# Regulator.net
KiCad netlist of a schematic drawn in EAGLE
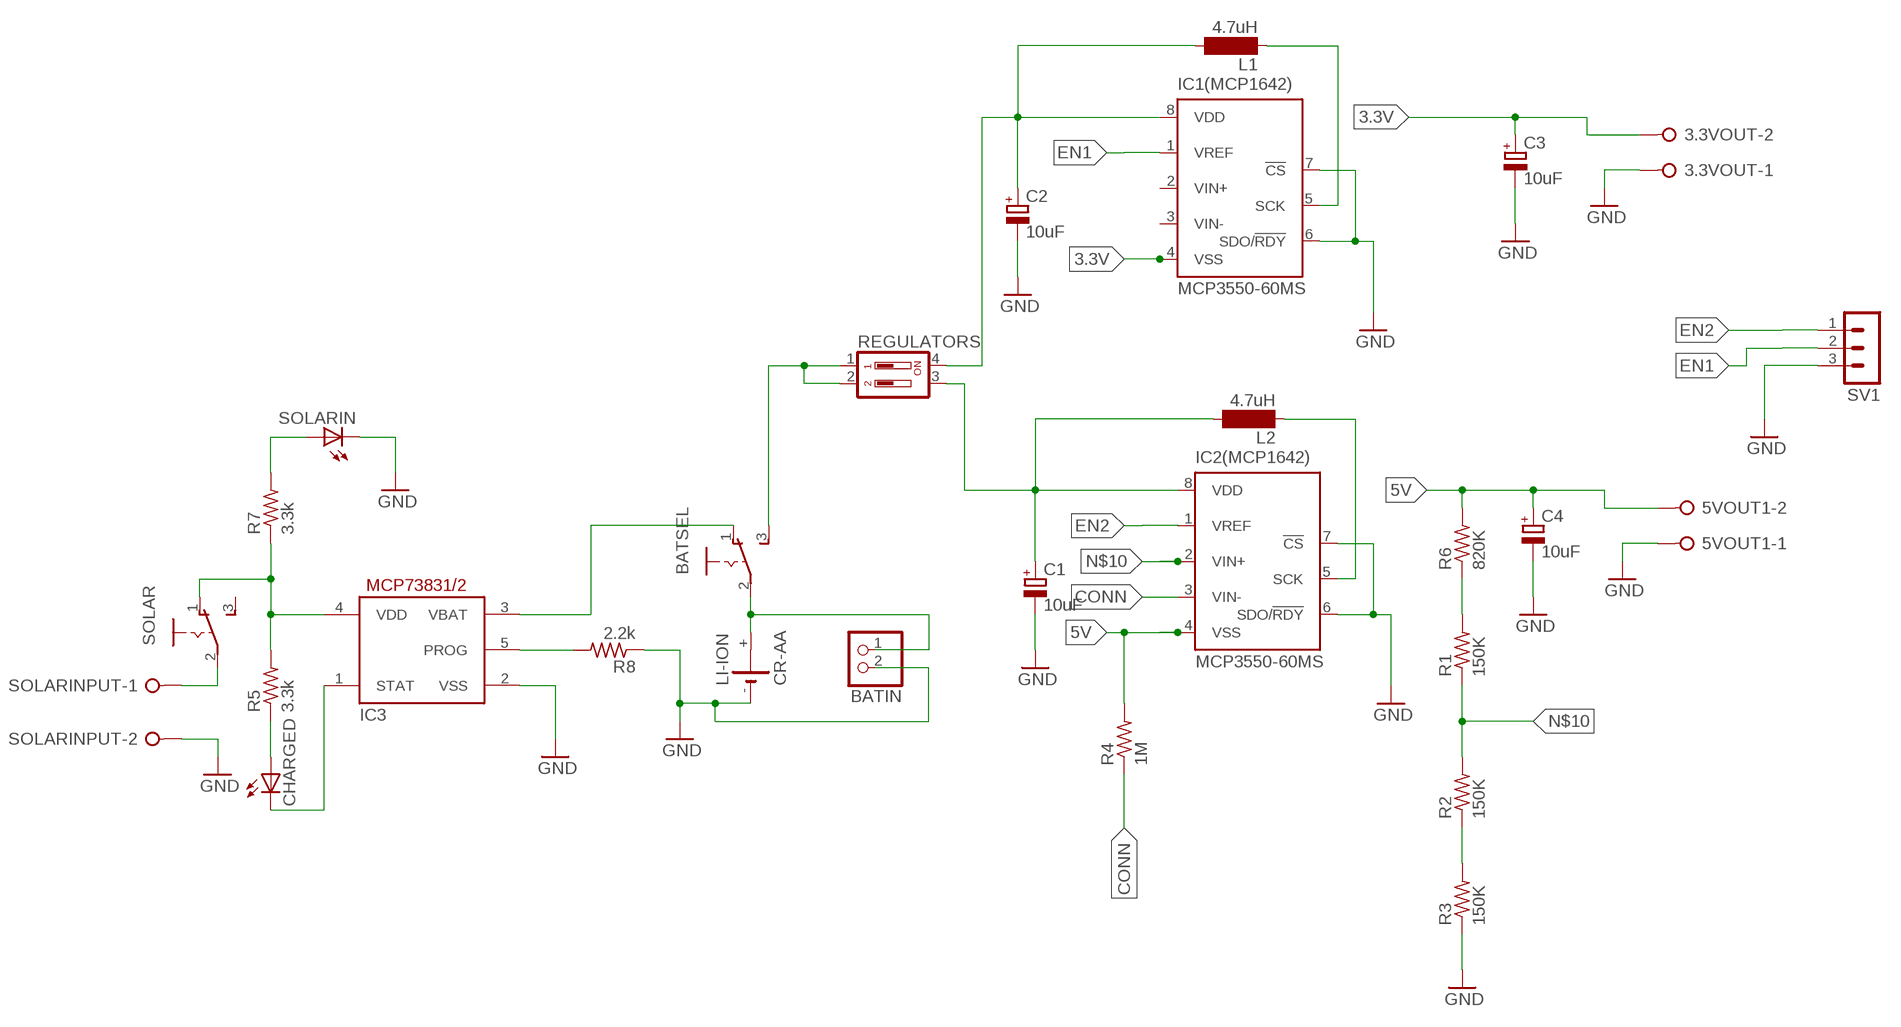
[diagram p0: schematic, sheet 1]

(export (version "E")
  (design (tool "Eeschema 10.0.6"))
  (components
    (comp (ref "3.3VOUT")
      (value "W237-02P")
      (footprint "eagle-import:W237-132")
      (libsource (lib "eagle-import") (part "W237-02P"))
    )
    (comp (ref "5VOUT1")
      (value "W237-02P")
      (footprint "eagle-import:W237-132")
      (libsource (lib "eagle-import") (part "W237-02P"))
    )
    (comp (ref "BATIN")
      (value "JST_2PIN-THM")
      (footprint "eagle-import:JST-PH-2-THM")
      (libsource (lib "eagle-import") (part "JST_2PIN-THM"))
    )
    (comp (ref "BATSEL")
      (value "255SB")
      (footprint "eagle-import:255SB")
      (libsource (lib "eagle-import") (part "255SB"))
    )
    (comp (ref "C1")
      (value "10uF")
      (footprint "eagle-import:140CLH-1010")
      (libsource (lib "eagle-import") (part "CPOL-EU140CLH-1010"))
    )
    (comp (ref "C2")
      (value "10uF")
      (footprint "eagle-import:140CLH-1010")
      (libsource (lib "eagle-import") (part "CPOL-EU140CLH-1010"))
    )
    (comp (ref "C3")
      (value "10uF")
      (footprint "eagle-import:140CLH-1010")
      (libsource (lib "eagle-import") (part "CPOL-EU140CLH-1010"))
    )
    (comp (ref "C4")
      (value "10uF")
      (footprint "eagle-import:140CLH-1010")
      (libsource (lib "eagle-import") (part "CPOL-EU140CLH-1010"))
    )
    (comp (ref "CHARGED")
      (value "LEDCHIP-LED0603")
      (footprint "eagle-import:CHIP-LED0603")
      (libsource (lib "eagle-import") (part "LEDCHIP-LED0603"))
    )
    (comp (ref "IC1(MCP1642)")
      (value "MCP3550-60MS")
      (footprint "eagle-import:MSOP8")
      (fields (field (name "MF") "MICROCHIP") (field (name "MPN") "MCP3550-60E/MS"))
      (libsource (lib "eagle-import") (part "MCP355MS0-60"))
    )
    (comp (ref "IC2(MCP1642)")
      (value "MCP3550-60MS")
      (footprint "eagle-import:MSOP8")
      (fields (field (name "MF") "MICROCHIP") (field (name "MPN") "MCP3550-60E/MS"))
      (libsource (lib "eagle-import") (part "MCP355MS0-60"))
    )
    (comp (ref "IC3")
      (value "MCP73831/OT")
      (footprint "eagle-import:SOT23-5L")
      (libsource (lib "eagle-import") (part "MCP73831/OT"))
    )
    (comp (ref "L1")
      (value "4.7uH")
      (footprint "eagle-import:MS85")
      (libsource (lib "eagle-import") (part "MS85"))
    )
    (comp (ref "L2")
      (value "4.7uH")
      (footprint "eagle-import:MS85")
      (libsource (lib "eagle-import") (part "MS85"))
    )
    (comp (ref "LI-ION")
      (value "CR-AA")
      (footprint "eagle-import:CRAA")
      (libsource (lib "eagle-import") (part "CR-AA"))
    )
    (comp (ref "R1")
      (value "150K")
      (footprint "eagle-import:M0805")
      (libsource (lib "eagle-import") (part "R-US_M0805"))
    )
    (comp (ref "R2")
      (value "150K")
      (footprint "eagle-import:M0805")
      (libsource (lib "eagle-import") (part "R-US_M0805"))
    )
    (comp (ref "R3")
      (value "150K")
      (footprint "eagle-import:M0805")
      (libsource (lib "eagle-import") (part "R-US_M0805"))
    )
    (comp (ref "R4")
      (value "1M")
      (footprint "eagle-import:M0805")
      (libsource (lib "eagle-import") (part "R-US_M0805"))
    )
    (comp (ref "R5")
      (value "3.3k")
      (footprint "eagle-import:M3216")
      (libsource (lib "eagle-import") (part "R-US_M3216"))
    )
    (comp (ref "R6")
      (value "820K")
      (footprint "eagle-import:M0805")
      (libsource (lib "eagle-import") (part "R-US_M0805"))
    )
    (comp (ref "R7")
      (value "3.3k")
      (footprint "eagle-import:M3216")
      (libsource (lib "eagle-import") (part "R-US_M3216"))
    )
    (comp (ref "R8")
      (value "2.2k")
      (footprint "eagle-import:M3216")
      (libsource (lib "eagle-import") (part "R-US_M3216"))
    )
    (comp (ref "REGULATORS")
      (value "DIP02YL")
      (footprint "eagle-import:DIP02YL")
      (libsource (lib "eagle-import") (part "DIP02YL"))
    )
    (comp (ref "SOLAR")
      (value "255SB")
      (footprint "eagle-import:255SB")
      (libsource (lib "eagle-import") (part "255SB"))
    )
    (comp (ref "SOLARIN")
      (value "LEDCHIP-LED0603")
      (footprint "eagle-import:CHIP-LED0603")
      (libsource (lib "eagle-import") (part "LEDCHIP-LED0603"))
    )
    (comp (ref "SOLARINPUT")
      (value "W237-02P")
      (footprint "eagle-import:W237-132")
      (libsource (lib "eagle-import") (part "W237-02P"))
    )
    (comp (ref "SV1")
      (value "MA03-1")
      (footprint "eagle-import:MA03-1")
      (libsource (lib "eagle-import") (part "MA03-1"))
    )
  )
  (nets
    (net (code "1") (name "3.3V") (class "Default")
      (node (ref "3.3VOUT") (pin "2") (pinfunction "KL_2") (pintype "passive"))
      (node (ref "C3") (pin "+") (pinfunction "+_+") (pintype "passive"))
      (node (ref "IC1(MCP1642)") (pin "4") (pinfunction "VSS_4") (pintype "power_in"))
    )
    (net (code "2") (name "5V") (class "Default")
      (node (ref "5VOUT1") (pin "2") (pinfunction "KL_2") (pintype "passive"))
      (node (ref "C4") (pin "+") (pinfunction "+_+") (pintype "passive"))
      (node (ref "IC2(MCP1642)") (pin "4") (pinfunction "VSS_4") (pintype "power_in"))
      (node (ref "R4") (pin "2") (pinfunction "2_2") (pintype "passive"))
      (node (ref "R6") (pin "2") (pinfunction "2_2") (pintype "passive"))
    )
    (net (code "3") (name "CONN") (class "Default")
      (node (ref "IC2(MCP1642)") (pin "3") (pinfunction "VIN-_3") (pintype "input"))
      (node (ref "R4") (pin "1") (pinfunction "1_1") (pintype "passive"))
    )
    (net (code "4") (name "EN1") (class "Default")
      (node (ref "IC1(MCP1642)") (pin "1") (pinfunction "VREF_1") (pintype "input"))
      (node (ref "SV1") (pin "2") (pinfunction "2_2") (pintype "passive"))
    )
    (net (code "5") (name "EN2") (class "Default")
      (node (ref "IC2(MCP1642)") (pin "1") (pinfunction "VREF_1") (pintype "input"))
      (node (ref "SV1") (pin "1") (pinfunction "1_1") (pintype "passive"))
    )
    (net (code "6") (name "GND") (class "Default")
      (node (ref "3.3VOUT") (pin "1") (pinfunction "KL_1") (pintype "passive"))
      (node (ref "5VOUT1") (pin "1") (pinfunction "KL_1") (pintype "passive"))
      (node (ref "BATIN") (pin "2") (pinfunction "1_2") (pintype "passive"))
      (node (ref "C1") (pin "-") (pinfunction "-_-") (pintype "passive"))
      (node (ref "C2") (pin "-") (pinfunction "-_-") (pintype "passive"))
      (node (ref "C3") (pin "-") (pinfunction "-_-") (pintype "passive"))
      (node (ref "C4") (pin "-") (pinfunction "-_-") (pintype "passive"))
      (node (ref "IC1(MCP1642)") (pin "6") (pinfunction "SDO/~{RDY}_6") (pintype "output"))
      (node (ref "IC1(MCP1642)") (pin "7") (pinfunction "~{CS}_7") (pintype "input"))
      (node (ref "IC2(MCP1642)") (pin "6") (pinfunction "SDO/~{RDY}_6") (pintype "output"))
      (node (ref "IC2(MCP1642)") (pin "7") (pinfunction "~{CS}_7") (pintype "input"))
      (node (ref "IC3") (pin "2") (pinfunction "VSS_2") (pintype "power_in"))
      (node (ref "LI-ION") (pin "-") (pinfunction "-_-") (pintype "passive"))
      (node (ref "R3") (pin "1") (pinfunction "1_1") (pintype "passive"))
      (node (ref "R8") (pin "1") (pinfunction "1_1") (pintype "passive"))
      (node (ref "SOLARIN") (pin "C") (pinfunction "C_C") (pintype "passive"))
      (node (ref "SOLARINPUT") (pin "2") (pinfunction "KL_2") (pintype "passive"))
      (node (ref "SV1") (pin "3") (pinfunction "3_3") (pintype "passive"))
    )
    (net (code "7") (name "N$10") (class "Default")
      (node (ref "IC2(MCP1642)") (pin "2") (pinfunction "VIN+_2") (pintype "input"))
      (node (ref "R1") (pin "1") (pinfunction "1_1") (pintype "passive"))
      (node (ref "R2") (pin "2") (pinfunction "2_2") (pintype "passive"))
    )
    (net (code "8") (name "Net-(BATIN-2)") (class "Default")
      (node (ref "BATIN") (pin "1") (pinfunction "2_1") (pintype "passive"))
      (node (ref "BATSEL") (pin "2") (pinfunction "P_2") (pintype "passive"))
      (node (ref "LI-ION") (pin "+") (pinfunction "+_+") (pintype "passive"))
    )
    (net (code "9") (name "Net-(BATSEL-O)") (class "Default")
      (node (ref "BATSEL") (pin "1") (pinfunction "O_1") (pintype "passive"))
      (node (ref "IC3") (pin "3") (pinfunction "VBAT_3") (pintype "bidirectional"))
    )
    (net (code "10") (name "Net-(BATSEL-S)") (class "Default")
      (node (ref "BATSEL") (pin "3") (pinfunction "S_3") (pintype "passive"))
      (node (ref "REGULATORS") (pin "1") (pinfunction "1_1") (pintype "passive"))
      (node (ref "REGULATORS") (pin "2") (pinfunction "2_2") (pintype "passive"))
    )
    (net (code "11") (name "Net-(CHARGED-PadA)") (class "Default")
      (node (ref "CHARGED") (pin "A") (pinfunction "A_A") (pintype "passive"))
      (node (ref "R5") (pin "1") (pinfunction "1_1") (pintype "passive"))
    )
    (net (code "12") (name "Net-(IC1(MCP1642)-SCK)") (class "Default")
      (node (ref "IC1(MCP1642)") (pin "5") (pinfunction "SCK_5") (pintype "input"))
      (node (ref "L1") (pin "1") (pinfunction "1_1") (pintype "passive"))
    )
    (net (code "13") (name "Net-(IC1(MCP1642)-VDD)") (class "Default")
      (node (ref "C2") (pin "+") (pinfunction "+_+") (pintype "passive"))
      (node (ref "IC1(MCP1642)") (pin "8") (pinfunction "VDD_8") (pintype "power_in"))
      (node (ref "L1") (pin "2") (pinfunction "2_2") (pintype "passive"))
      (node (ref "REGULATORS") (pin "4") (pinfunction "4_4") (pintype "passive"))
    )
    (net (code "14") (name "Net-(IC2(MCP1642)-SCK)") (class "Default")
      (node (ref "IC2(MCP1642)") (pin "5") (pinfunction "SCK_5") (pintype "input"))
      (node (ref "L2") (pin "1") (pinfunction "1_1") (pintype "passive"))
    )
    (net (code "15") (name "Net-(IC2(MCP1642)-VDD)") (class "Default")
      (node (ref "C1") (pin "+") (pinfunction "+_+") (pintype "passive"))
      (node (ref "IC2(MCP1642)") (pin "8") (pinfunction "VDD_8") (pintype "power_in"))
      (node (ref "L2") (pin "2") (pinfunction "2_2") (pintype "passive"))
      (node (ref "REGULATORS") (pin "3") (pinfunction "3_3") (pintype "passive"))
    )
    (net (code "16") (name "Net-(IC3-PROG)") (class "Default")
      (node (ref "IC3") (pin "5") (pinfunction "PROG_5") (pintype "input"))
      (node (ref "R8") (pin "2") (pinfunction "2_2") (pintype "passive"))
    )
    (net (code "17") (name "Net-(IC3-STAT)") (class "Default")
      (node (ref "CHARGED") (pin "C") (pinfunction "C_C") (pintype "passive"))
      (node (ref "IC3") (pin "1") (pinfunction "STAT_1") (pintype "output"))
    )
    (net (code "18") (name "Net-(IC3-VDD)") (class "Default")
      (node (ref "IC3") (pin "4") (pinfunction "VDD_4") (pintype "power_in"))
      (node (ref "R5") (pin "2") (pinfunction "2_2") (pintype "passive"))
      (node (ref "R7") (pin "1") (pinfunction "1_1") (pintype "passive"))
      (node (ref "SOLAR") (pin "1") (pinfunction "O_1") (pintype "passive"))
    )
    (net (code "19") (name "Net-(R1-Pad2)") (class "Default")
      (node (ref "R1") (pin "2") (pinfunction "2_2") (pintype "passive"))
      (node (ref "R6") (pin "1") (pinfunction "1_1") (pintype "passive"))
    )
    (net (code "20") (name "Net-(R2-Pad1)") (class "Default")
      (node (ref "R2") (pin "1") (pinfunction "1_1") (pintype "passive"))
      (node (ref "R3") (pin "2") (pinfunction "2_2") (pintype "passive"))
    )
    (net (code "21") (name "Net-(R7-Pad2)") (class "Default")
      (node (ref "R7") (pin "2") (pinfunction "2_2") (pintype "passive"))
      (node (ref "SOLARIN") (pin "A") (pinfunction "A_A") (pintype "passive"))
    )
    (net (code "22") (name "Net-(SOLAR-P)") (class "Default")
      (node (ref "SOLAR") (pin "2") (pinfunction "P_2") (pintype "passive"))
      (node (ref "SOLARINPUT") (pin "1") (pinfunction "KL_1") (pintype "passive"))
    )
    (net (code "23") (name "unconnected-(IC1(MCP1642)-VIN+-Pad2)") (class "Default")
      (node (ref "IC1(MCP1642)") (pin "2") (pinfunction "VIN+_2") (pintype "input"))
    )
    (net (code "24") (name "unconnected-(IC1(MCP1642)-VIN--Pad3)") (class "Default")
      (node (ref "IC1(MCP1642)") (pin "3") (pinfunction "VIN-_3") (pintype "input"))
    )
    (net (code "25") (name "unconnected-(LI-ION-+-Pad+@1)") (class "Default")
      (node (ref "LI-ION") (pin "+@1") (pinfunction "+_+@1") (pintype "passive"))
    )
    (net (code "26") (name "unconnected-(SOLAR-S-Pad3)") (class "Default")
      (node (ref "SOLAR") (pin "3") (pinfunction "S_3") (pintype "passive"))
    )
  )
)
